# Memory_SDRAM.net
KiCad netlist of a schematic drawn in Altium Designer
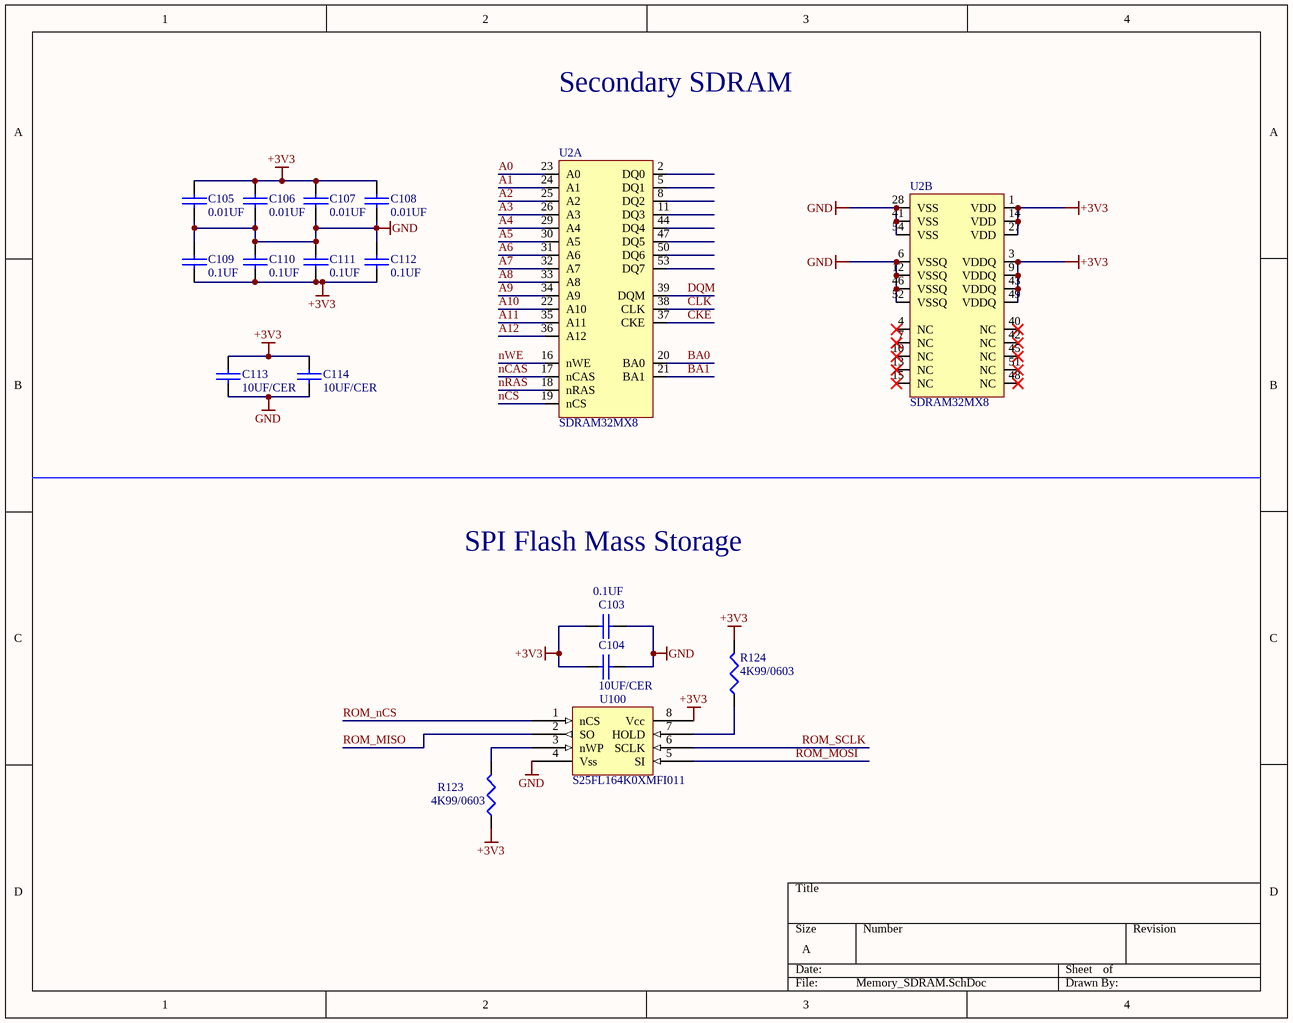
[diagram p0: Memory_SDRAM.SchDoc]

(export (version "E")
  (design (tool "Eeschema 10.0.6"))
  (components
    (comp (ref "C103")
      (value "0.1UF")
      (footprint "0603")
      (description "CAP .10UF 16V CERAMIC X7R 0603")
      (fields (field (name "MFG") "Kemet"))
      (libsource (lib "C64Interface") (part "0.1UF"))
    )
    (comp (ref "C104")
      (value "10UF/CER")
      (footprint "0805")
      (description "10µF ±10% 25V Ceramic Capacitor X7S 0805")
      (libsource (lib "*") (part "10UF/CER"))
    )
    (comp (ref "C105")
      (value "0.01UF")
      (footprint "0603")
      (description "10000pF ±10% 10V Ceramic Capacitor X7R 0603 (1608 Metric)")
      (fields (field (name "MFG") "Kemet"))
      (libsource (lib "C64Interface") (part "0.01UF"))
    )
    (comp (ref "C106")
      (value "0.01UF")
      (footprint "0603")
      (description "10000pF ±10% 10V Ceramic Capacitor X7R 0603 (1608 Metric)")
      (fields (field (name "MFG") "Kemet"))
      (libsource (lib "C64Interface") (part "0.01UF"))
    )
    (comp (ref "C107")
      (value "0.01UF")
      (footprint "0603")
      (description "10000pF ±10% 10V Ceramic Capacitor X7R 0603 (1608 Metric)")
      (fields (field (name "MFG") "Kemet"))
      (libsource (lib "C64Interface") (part "0.01UF"))
    )
    (comp (ref "C108")
      (value "0.01UF")
      (footprint "0603")
      (description "10000pF ±10% 10V Ceramic Capacitor X7R 0603 (1608 Metric)")
      (fields (field (name "MFG") "Kemet"))
      (libsource (lib "C64Interface") (part "0.01UF"))
    )
    (comp (ref "C109")
      (value "0.1UF")
      (footprint "0603")
      (description "CAP .10UF 16V CERAMIC X7R 0603")
      (fields (field (name "MFG") "Kemet"))
      (libsource (lib "C64Interface") (part "0.1UF"))
    )
    (comp (ref "C110")
      (value "0.1UF")
      (footprint "0603")
      (description "CAP .10UF 16V CERAMIC X7R 0603")
      (fields (field (name "MFG") "Kemet"))
      (libsource (lib "C64Interface") (part "0.1UF"))
    )
    (comp (ref "C111")
      (value "0.1UF")
      (footprint "0603")
      (description "CAP .10UF 16V CERAMIC X7R 0603")
      (fields (field (name "MFG") "Kemet"))
      (libsource (lib "C64Interface") (part "0.1UF"))
    )
    (comp (ref "C112")
      (value "0.1UF")
      (footprint "0603")
      (description "CAP .10UF 16V CERAMIC X7R 0603")
      (fields (field (name "MFG") "Kemet"))
      (libsource (lib "C64Interface") (part "0.1UF"))
    )
    (comp (ref "C113")
      (value "10UF/CER")
      (footprint "0805")
      (description "10µF ±10% 25V Ceramic Capacitor X7S 0805")
      (libsource (lib "C64Interface") (part "10UF/CER"))
    )
    (comp (ref "C114")
      (value "10UF/CER")
      (footprint "0805")
      (description "10µF ±10% 25V Ceramic Capacitor X7S 0805")
      (libsource (lib "C64Interface") (part "10UF/CER"))
    )
    (comp (ref "R123")
      (value "4K99/0603")
      (footprint "0603")
      (description "RES 4.99K OHM 1/10W 1% 0603 SMD")
      (fields (field (name "MFG") "Dale/Vishay"))
      (libsource (lib "C64Interface") (part "4K99/0603"))
    )
    (comp (ref "R124")
      (value "4K99/0603")
      (footprint "0603")
      (description "RES 4.99K OHM 1/10W 1% 0603 SMD")
      (fields (field (name "MFG") "Dale/Vishay"))
      (libsource (lib "C64Interface") (part "4K99/0603"))
    )
    (comp (ref "U2")
      (value "SDRAM32MX8")
      (footprint "SOP54")
      (description "SDRAM Memory IC 256Mb (32M x 8) Parallel 166MHz 5.5ns 54-TSOP II")
      (fields (field (name "MFG") "Alliance Memory"))
      (libsource (lib "C64Interface") (part "SDRAM32MX8"))
    )
    (comp (ref "U100")
      (value "S25FL164K0XMFI011")
      (footprint "SO-8")
      (description "IC FLASH 64MBIT 108MHZ 8SOIC")
      (libsource (lib "*") (part "S25FL164K0XMFI011"))
    )
  )
  (nets
    (net (code "1") (name "+3V3") (class "Default")
      (node (ref "C103") (pin "1") (pintype "passive"))
      (node (ref "C104") (pin "1") (pintype "passive"))
      (node (ref "C105") (pin "1") (pintype "passive"))
      (node (ref "C106") (pin "1") (pintype "passive"))
      (node (ref "C107") (pin "1") (pintype "passive"))
      (node (ref "C108") (pin "1") (pintype "passive"))
      (node (ref "C109") (pin "2") (pintype "passive"))
      (node (ref "C110") (pin "2") (pintype "passive"))
      (node (ref "C111") (pin "2") (pintype "passive"))
      (node (ref "C112") (pin "2") (pintype "passive"))
      (node (ref "C113") (pin "2") (pintype "passive"))
      (node (ref "C114") (pin "2") (pintype "passive"))
      (node (ref "R123") (pin "1") (pintype "passive"))
      (node (ref "R124") (pin "2") (pintype "passive"))
      (node (ref "U100") (pin "8") (pinfunction "Vcc_8") (pintype "power_in"))
      (node (ref "U2") (pin "1") (pinfunction "VDD_1") (pintype "passive"))
      (node (ref "U2") (pin "14") (pinfunction "VDD_14") (pintype "passive"))
      (node (ref "U2") (pin "27") (pinfunction "VDD_27") (pintype "passive"))
      (node (ref "U2") (pin "3") (pinfunction "VDDQ_3") (pintype "passive"))
      (node (ref "U2") (pin "43") (pinfunction "VDDQ_43") (pintype "passive"))
      (node (ref "U2") (pin "49") (pinfunction "VDDQ_49") (pintype "passive"))
      (node (ref "U2") (pin "9") (pinfunction "VDDQ_9") (pintype "passive"))
    )
    (net (code "2") (name "/A0") (class "Default")
      (node (ref "U2") (pin "23") (pinfunction "A0_23") (pintype "passive"))
    )
    (net (code "3") (name "/A1") (class "Default")
      (node (ref "U2") (pin "24") (pinfunction "A1_24") (pintype "passive"))
    )
    (net (code "4") (name "/A2") (class "Default")
      (node (ref "U2") (pin "25") (pinfunction "A2_25") (pintype "passive"))
    )
    (net (code "5") (name "/A3") (class "Default")
      (node (ref "U2") (pin "26") (pinfunction "A3_26") (pintype "passive"))
    )
    (net (code "6") (name "/A4") (class "Default")
      (node (ref "U2") (pin "29") (pinfunction "A4_29") (pintype "passive"))
    )
    (net (code "7") (name "/A5") (class "Default")
      (node (ref "U2") (pin "30") (pinfunction "A5_30") (pintype "passive"))
    )
    (net (code "8") (name "/A6") (class "Default")
      (node (ref "U2") (pin "31") (pinfunction "A6_31") (pintype "passive"))
    )
    (net (code "9") (name "/A7") (class "Default")
      (node (ref "U2") (pin "32") (pinfunction "A7_32") (pintype "passive"))
    )
    (net (code "10") (name "/A8") (class "Default")
      (node (ref "U2") (pin "33") (pinfunction "A8_33") (pintype "passive"))
    )
    (net (code "11") (name "/A9") (class "Default")
      (node (ref "U2") (pin "34") (pinfunction "A9_34") (pintype "passive"))
    )
    (net (code "12") (name "/A10") (class "Default")
      (node (ref "U2") (pin "22") (pinfunction "A10_22") (pintype "passive"))
    )
    (net (code "13") (name "/A11") (class "Default")
      (node (ref "U2") (pin "35") (pinfunction "A11_35") (pintype "passive"))
    )
    (net (code "14") (name "/A12") (class "Default")
      (node (ref "U2") (pin "36") (pinfunction "A12_36") (pintype "passive"))
    )
    (net (code "15") (name "/BA0") (class "Default")
      (node (ref "U2") (pin "20") (pinfunction "BA0_20") (pintype "passive"))
    )
    (net (code "16") (name "/BA1") (class "Default")
      (node (ref "U2") (pin "21") (pinfunction "BA1_21") (pintype "passive"))
    )
    (net (code "17") (name "/CKE") (class "Default")
      (node (ref "U2") (pin "37") (pinfunction "CKE_37") (pintype "passive"))
    )
    (net (code "18") (name "/CLK") (class "Default")
      (node (ref "U2") (pin "38") (pinfunction "CLK_38") (pintype "passive"))
    )
    (net (code "19") (name "/DQM") (class "Default")
      (node (ref "U2") (pin "39") (pinfunction "DQM_39") (pintype "passive"))
    )
    (net (code "20") (name "/ROM_MISO") (class "Default")
      (node (ref "U100") (pin "2") (pinfunction "SO_2") (pintype "output"))
    )
    (net (code "21") (name "/ROM_MOSI") (class "Default")
      (node (ref "U100") (pin "5") (pinfunction "SI_5") (pintype "input"))
    )
    (net (code "22") (name "/ROM_SCLK") (class "Default")
      (node (ref "U100") (pin "6") (pinfunction "SCLK_6") (pintype "input"))
    )
    (net (code "23") (name "/ROM_nCS") (class "Default")
      (node (ref "U100") (pin "1") (pinfunction "nCS_1") (pintype "input"))
    )
    (net (code "24") (name "/nCAS") (class "Default")
      (node (ref "U2") (pin "17") (pinfunction "nCAS_17") (pintype "passive"))
    )
    (net (code "25") (name "/nCS") (class "Default")
      (node (ref "U2") (pin "19") (pinfunction "nCS_19") (pintype "passive"))
    )
    (net (code "26") (name "/nRAS") (class "Default")
      (node (ref "U2") (pin "18") (pinfunction "nRAS_18") (pintype "passive"))
    )
    (net (code "27") (name "/nWE") (class "Default")
      (node (ref "U2") (pin "16") (pinfunction "nWE_16") (pintype "passive"))
    )
    (net (code "28") (name "GND") (class "Default")
      (node (ref "C103") (pin "2") (pintype "passive"))
      (node (ref "C104") (pin "2") (pintype "passive"))
      (node (ref "C105") (pin "2") (pintype "passive"))
      (node (ref "C106") (pin "2") (pintype "passive"))
      (node (ref "C107") (pin "2") (pintype "passive"))
      (node (ref "C108") (pin "2") (pintype "passive"))
      (node (ref "C109") (pin "1") (pintype "passive"))
      (node (ref "C110") (pin "1") (pintype "passive"))
      (node (ref "C111") (pin "1") (pintype "passive"))
      (node (ref "C112") (pin "1") (pintype "passive"))
      (node (ref "C113") (pin "1") (pintype "passive"))
      (node (ref "C114") (pin "1") (pintype "passive"))
      (node (ref "U100") (pin "4") (pinfunction "Vss_4") (pintype "power_in"))
      (node (ref "U2") (pin "12") (pinfunction "VSSQ_12") (pintype "passive"))
      (node (ref "U2") (pin "28") (pinfunction "VSS_28") (pintype "passive"))
      (node (ref "U2") (pin "41") (pinfunction "VSS_41") (pintype "passive"))
      (node (ref "U2") (pin "46") (pinfunction "VSSQ_46") (pintype "passive"))
      (node (ref "U2") (pin "52") (pinfunction "VSSQ_52") (pintype "passive"))
      (node (ref "U2") (pin "54") (pinfunction "VSS_54") (pintype "passive"))
      (node (ref "U2") (pin "6") (pinfunction "VSSQ_6") (pintype "passive"))
    )
    (net (code "29") (name "Net-(U100-HOLD)") (class "Default")
      (node (ref "R124") (pin "1") (pintype "passive"))
      (node (ref "U100") (pin "7") (pinfunction "HOLD_7") (pintype "input"))
    )
    (net (code "30") (name "Net-(U100-nWP)") (class "Default")
      (node (ref "R123") (pin "2") (pintype "passive"))
      (node (ref "U100") (pin "3") (pinfunction "nWP_3") (pintype "input"))
    )
    (net (code "31") (name "unconnected-(U2A-DQ0-Pad2)") (class "Default")
      (node (ref "U2") (pin "2") (pinfunction "DQ0_2") (pintype "passive"))
    )
    (net (code "32") (name "unconnected-(U2A-DQ1-Pad5)") (class "Default")
      (node (ref "U2") (pin "5") (pinfunction "DQ1_5") (pintype "passive"))
    )
    (net (code "33") (name "unconnected-(U2A-DQ2-Pad8)") (class "Default")
      (node (ref "U2") (pin "8") (pinfunction "DQ2_8") (pintype "passive"))
    )
    (net (code "34") (name "unconnected-(U2A-DQ3-Pad11)") (class "Default")
      (node (ref "U2") (pin "11") (pinfunction "DQ3_11") (pintype "passive"))
    )
    (net (code "35") (name "unconnected-(U2A-DQ4-Pad44)") (class "Default")
      (node (ref "U2") (pin "44") (pinfunction "DQ4_44") (pintype "passive"))
    )
    (net (code "36") (name "unconnected-(U2A-DQ5-Pad47)") (class "Default")
      (node (ref "U2") (pin "47") (pinfunction "DQ5_47") (pintype "passive"))
    )
    (net (code "37") (name "unconnected-(U2A-DQ6-Pad50)") (class "Default")
      (node (ref "U2") (pin "50") (pinfunction "DQ6_50") (pintype "passive"))
    )
    (net (code "38") (name "unconnected-(U2A-DQ7-Pad53)") (class "Default")
      (node (ref "U2") (pin "53") (pinfunction "DQ7_53") (pintype "passive"))
    )
    (net (code "39") (name "unconnected-(U2B-NC-Pad4)") (class "Default")
      (node (ref "U2") (pin "4") (pinfunction "NC_4") (pintype "passive+no_connect"))
    )
    (net (code "40") (name "unconnected-(U2B-NC-Pad7)") (class "Default")
      (node (ref "U2") (pin "7") (pinfunction "NC_7") (pintype "passive+no_connect"))
    )
    (net (code "41") (name "unconnected-(U2B-NC-Pad10)") (class "Default")
      (node (ref "U2") (pin "10") (pinfunction "NC_10") (pintype "passive+no_connect"))
    )
    (net (code "42") (name "unconnected-(U2B-NC-Pad13)") (class "Default")
      (node (ref "U2") (pin "13") (pinfunction "NC_13") (pintype "passive+no_connect"))
    )
    (net (code "43") (name "unconnected-(U2B-NC-Pad15)") (class "Default")
      (node (ref "U2") (pin "15") (pinfunction "NC_15") (pintype "passive+no_connect"))
    )
    (net (code "44") (name "unconnected-(U2B-NC-Pad40)") (class "Default")
      (node (ref "U2") (pin "40") (pinfunction "NC_40") (pintype "passive+no_connect"))
    )
    (net (code "45") (name "unconnected-(U2B-NC-Pad42)") (class "Default")
      (node (ref "U2") (pin "42") (pinfunction "NC_42") (pintype "passive+no_connect"))
    )
    (net (code "46") (name "unconnected-(U2B-NC-Pad45)") (class "Default")
      (node (ref "U2") (pin "45") (pinfunction "NC_45") (pintype "passive+no_connect"))
    )
    (net (code "47") (name "unconnected-(U2B-NC-Pad48)") (class "Default")
      (node (ref "U2") (pin "48") (pinfunction "NC_48") (pintype "passive+no_connect"))
    )
    (net (code "48") (name "unconnected-(U2B-NC-Pad51)") (class "Default")
      (node (ref "U2") (pin "51") (pinfunction "NC_51") (pintype "passive+no_connect"))
    )
  )
)
